# auto-discharge.net
KiCad netlist of a schematic drawn in Altium Designer
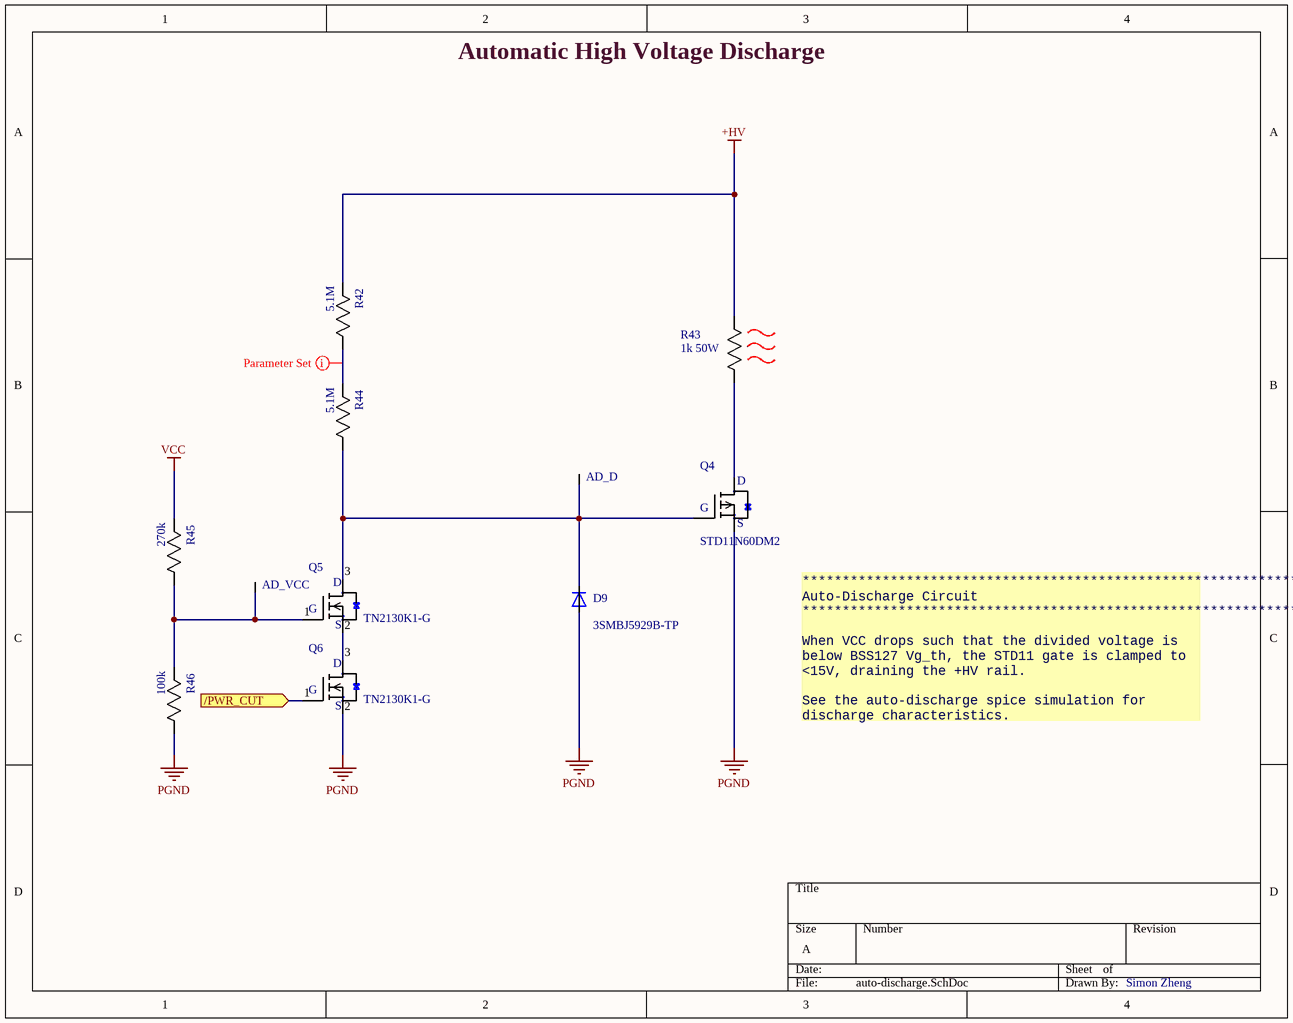
[diagram p0: auto-discharge.SchDoc]

(export (version "E")
  (design (tool "Eeschema 10.0.6"))
  (components
    (comp (ref "AD_D")
      (value "Test Point (Via)")
      (footprint "TP")
      (libsource (lib "AltiumLibraries") (part "Test Point (Via)"))
    )
    (comp (ref "AD_VCC")
      (value "Test Point (Via)")
      (footprint "TP")
      (libsource (lib "AltiumLibraries") (part "Test Point (Via)"))
    )
    (comp (ref "D9")
      (value "3SMBJ5929B-TP")
      (footprint "DO-214AA")
      (description "Diode ZENER 15V 3W")
      (libsource (lib "AltiumLibraries") (part "DIODE ZENER 15V 3W"))
    )
    (comp (ref "Q4")
      (value "STD11N60DM2")
      (footprint "DPAK (TO-252)")
      (fields (field (name "MFG") "STMicroelectronics"))
      (libsource (lib "AltiumLibraries") (part "STD11N60DM2"))
    )
    (comp (ref "Q5")
      (value "TN2130K1-G")
      (footprint "SOT95P237X112-3N")
      (description "N-Channel 300 V 85mA (Tj) 360mW (Tc) Surface Mount TO-236AB (SOT23)")
      (fields (field (name "COPYRIGHT") "Copyright (C) 2021 Ultra Librarian. All rights reserved."))
      (libsource (lib "AltiumLibraries") (part "MOSFET N-CH TN2130K1-G"))
    )
    (comp (ref "Q6")
      (value "TN2130K1-G")
      (footprint "SOT95P237X112-3N")
      (description "N-Channel 300 V 85mA (Tj) 360mW (Tc) Surface Mount TO-236AB (SOT23)")
      (fields (field (name "COPYRIGHT") "Copyright (C) 2021 Ultra Librarian. All rights reserved."))
      (libsource (lib "AltiumLibraries") (part "MOSFET N-CH TN2130K1-G"))
    )
    (comp (ref "R42")
      (value "5.1M")
      (footprint "0603")
      (description "RES SMD 5.1 MOHM 5% 1/8W 0805")
      (fields (field (name "TOLERANCE") "5%"))
      (libsource (lib "") (part "RES 5.1M 1/8W-5%_1"))
    )
    (comp (ref "R43")
      (value "1k 50W")
      (footprint "D2PAK (TO-263)")
      (description "RES SMD 1.5K OHM 1% 50W D2PAK")
      (fields (field (name "TOLERANCE") "1%"))
      (libsource (lib "AltiumLibraries") (part "RES 1.5k 50W"))
    )
    (comp (ref "R44")
      (value "5.1M")
      (footprint "0603")
      (description "RES SMD 5.1 MOHM 5% 1/8W 0805")
      (fields (field (name "TOLERANCE") "5%"))
      (libsource (lib "AltiumLibraries") (part "RES 5.1M 1/8W-5%"))
    )
    (comp (ref "R45")
      (value "270k")
      (footprint "0603")
      (description "RES SMD 270K OHM 5% 1/8W 0805/0603")
      (fields (field (name "TOLERANCE") "5%"))
      (libsource (lib "AltiumLibraries") (part "RES 270k 1/8W"))
    )
    (comp (ref "R46")
      (value "100k")
      (footprint "0603")
      (description "RES SMD 100K OHM 1% 1/8W 0805/0603")
      (fields (field (name "TOLERANCE") "1%"))
      (libsource (lib "AltiumLibraries") (part "RES 100k 1/8W - 1%"))
    )
  )
  (nets
    (net (code "1") (name "+HV") (class "Default")
      (node (ref "R42") (pin "2") (pinfunction "R2_2") (pintype "passive"))
      (node (ref "R43") (pin "2") (pinfunction "R2_2") (pintype "passive"))
    )
    (net (code "2") (name "/{slash}PWR_CUT") (class "Default")
      (node (ref "Q6") (pin "1") (pinfunction "G_1") (pintype "passive"))
    )
    (net (code "3") (name "Net-(Q5-D)") (class "Default")
      (node (ref "AD_D") (pin "1") (pinfunction "1_1") (pintype "passive"))
      (node (ref "D9") (pin "C") (pinfunction "C_C") (pintype "passive"))
      (node (ref "Q4") (pin "G") (pinfunction "G_G") (pintype "passive"))
      (node (ref "Q5") (pin "3") (pinfunction "D_3") (pintype "passive"))
      (node (ref "R44") (pin "1") (pinfunction "R1_1") (pintype "passive"))
    )
    (net (code "4") (name "Net-(Q5-G)") (class "Default")
      (node (ref "AD_VCC") (pin "1") (pinfunction "1_1") (pintype "passive"))
      (node (ref "Q5") (pin "1") (pinfunction "G_1") (pintype "passive"))
      (node (ref "R45") (pin "1") (pinfunction "R1_1") (pintype "passive"))
      (node (ref "R46") (pin "2") (pinfunction "R2_2") (pintype "passive"))
    )
    (net (code "5") (name "Net-(Q5-S)") (class "Default")
      (node (ref "Q5") (pin "2") (pinfunction "S_2") (pintype "passive"))
      (node (ref "Q6") (pin "3") (pinfunction "D_3") (pintype "passive"))
    )
    (net (code "6") (name "Net-(R42-R1)") (class "Default")
      (node (ref "R42") (pin "1") (pinfunction "R1_1") (pintype "passive"))
      (node (ref "R44") (pin "2") (pinfunction "R2_2") (pintype "passive"))
    )
    (net (code "7") (name "Net-(R43-R1)") (class "Default")
      (node (ref "Q4") (pin "D") (pinfunction "D_D") (pintype "passive"))
      (node (ref "R43") (pin "1") (pinfunction "R1_1") (pintype "passive"))
    )
    (net (code "8") (name "PGND") (class "Default")
      (node (ref "D9") (pin "A") (pinfunction "A_A") (pintype "passive"))
      (node (ref "Q4") (pin "S") (pinfunction "S_S") (pintype "passive"))
      (node (ref "Q6") (pin "2") (pinfunction "S_2") (pintype "passive"))
      (node (ref "R46") (pin "1") (pinfunction "R1_1") (pintype "passive"))
    )
    (net (code "9") (name "VCC") (class "Default")
      (node (ref "R45") (pin "2") (pinfunction "R2_2") (pintype "passive"))
    )
    (net (code "10") (name "unconnected-(R43-Pad3)") (class "Default")
      (node (ref "R43") (pin "3") (pinfunction "3_3") (pintype "passive"))
    )
  )
)
